# PIC_CONTROLLER.net
KiCad netlist of a schematic drawn in Altium Designer
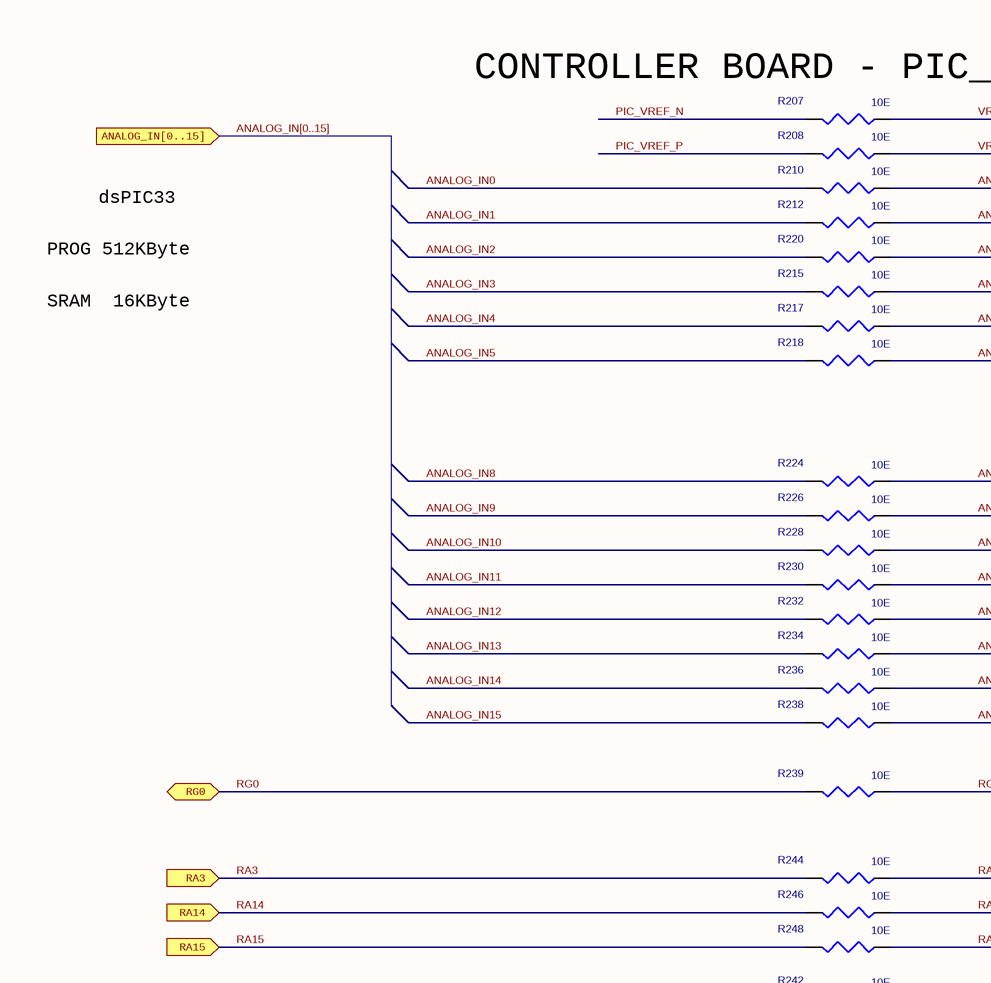
[diagram p0: PIC_CONTROLLER.SchDoc, top left]
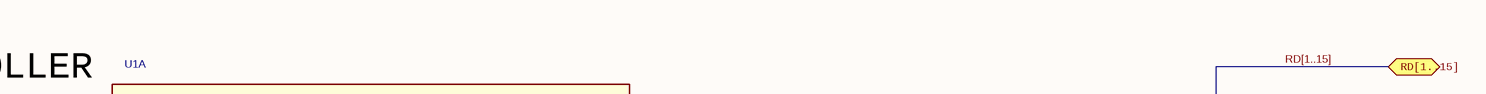
[diagram p1: PIC_CONTROLLER.SchDoc, top right]
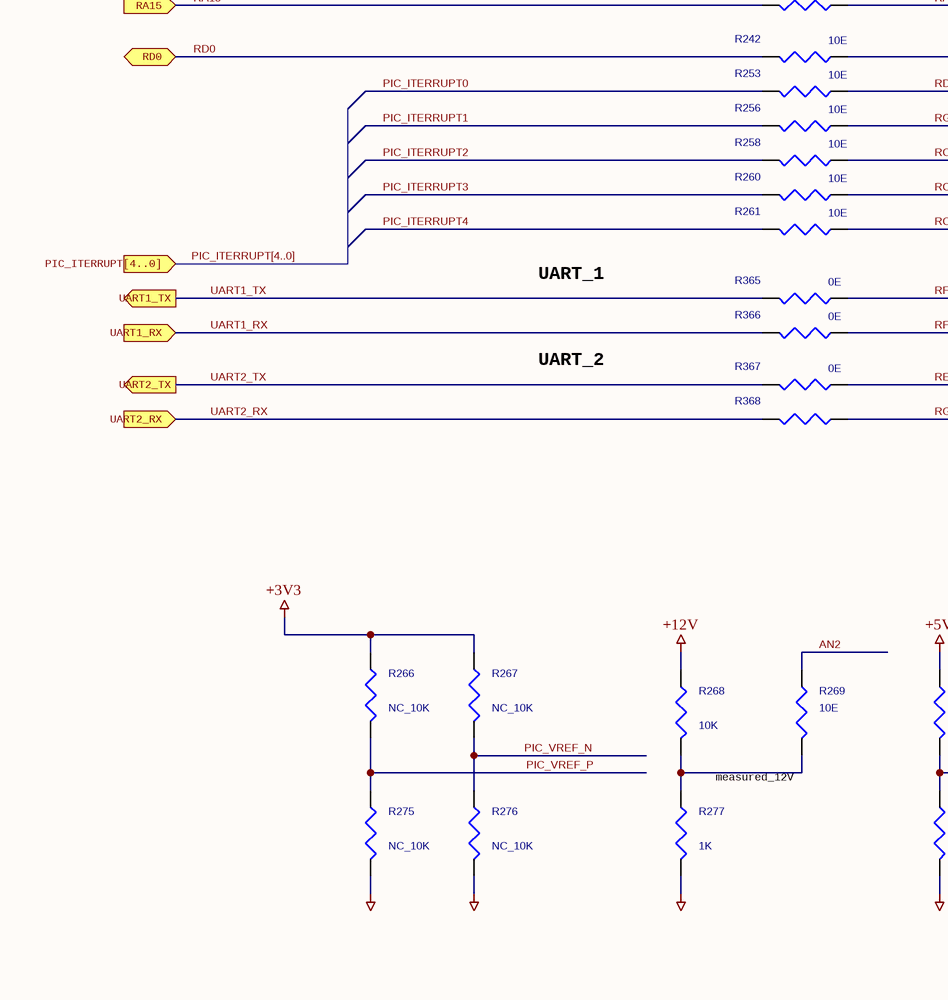
[diagram p2: PIC_CONTROLLER.SchDoc, bottom left]
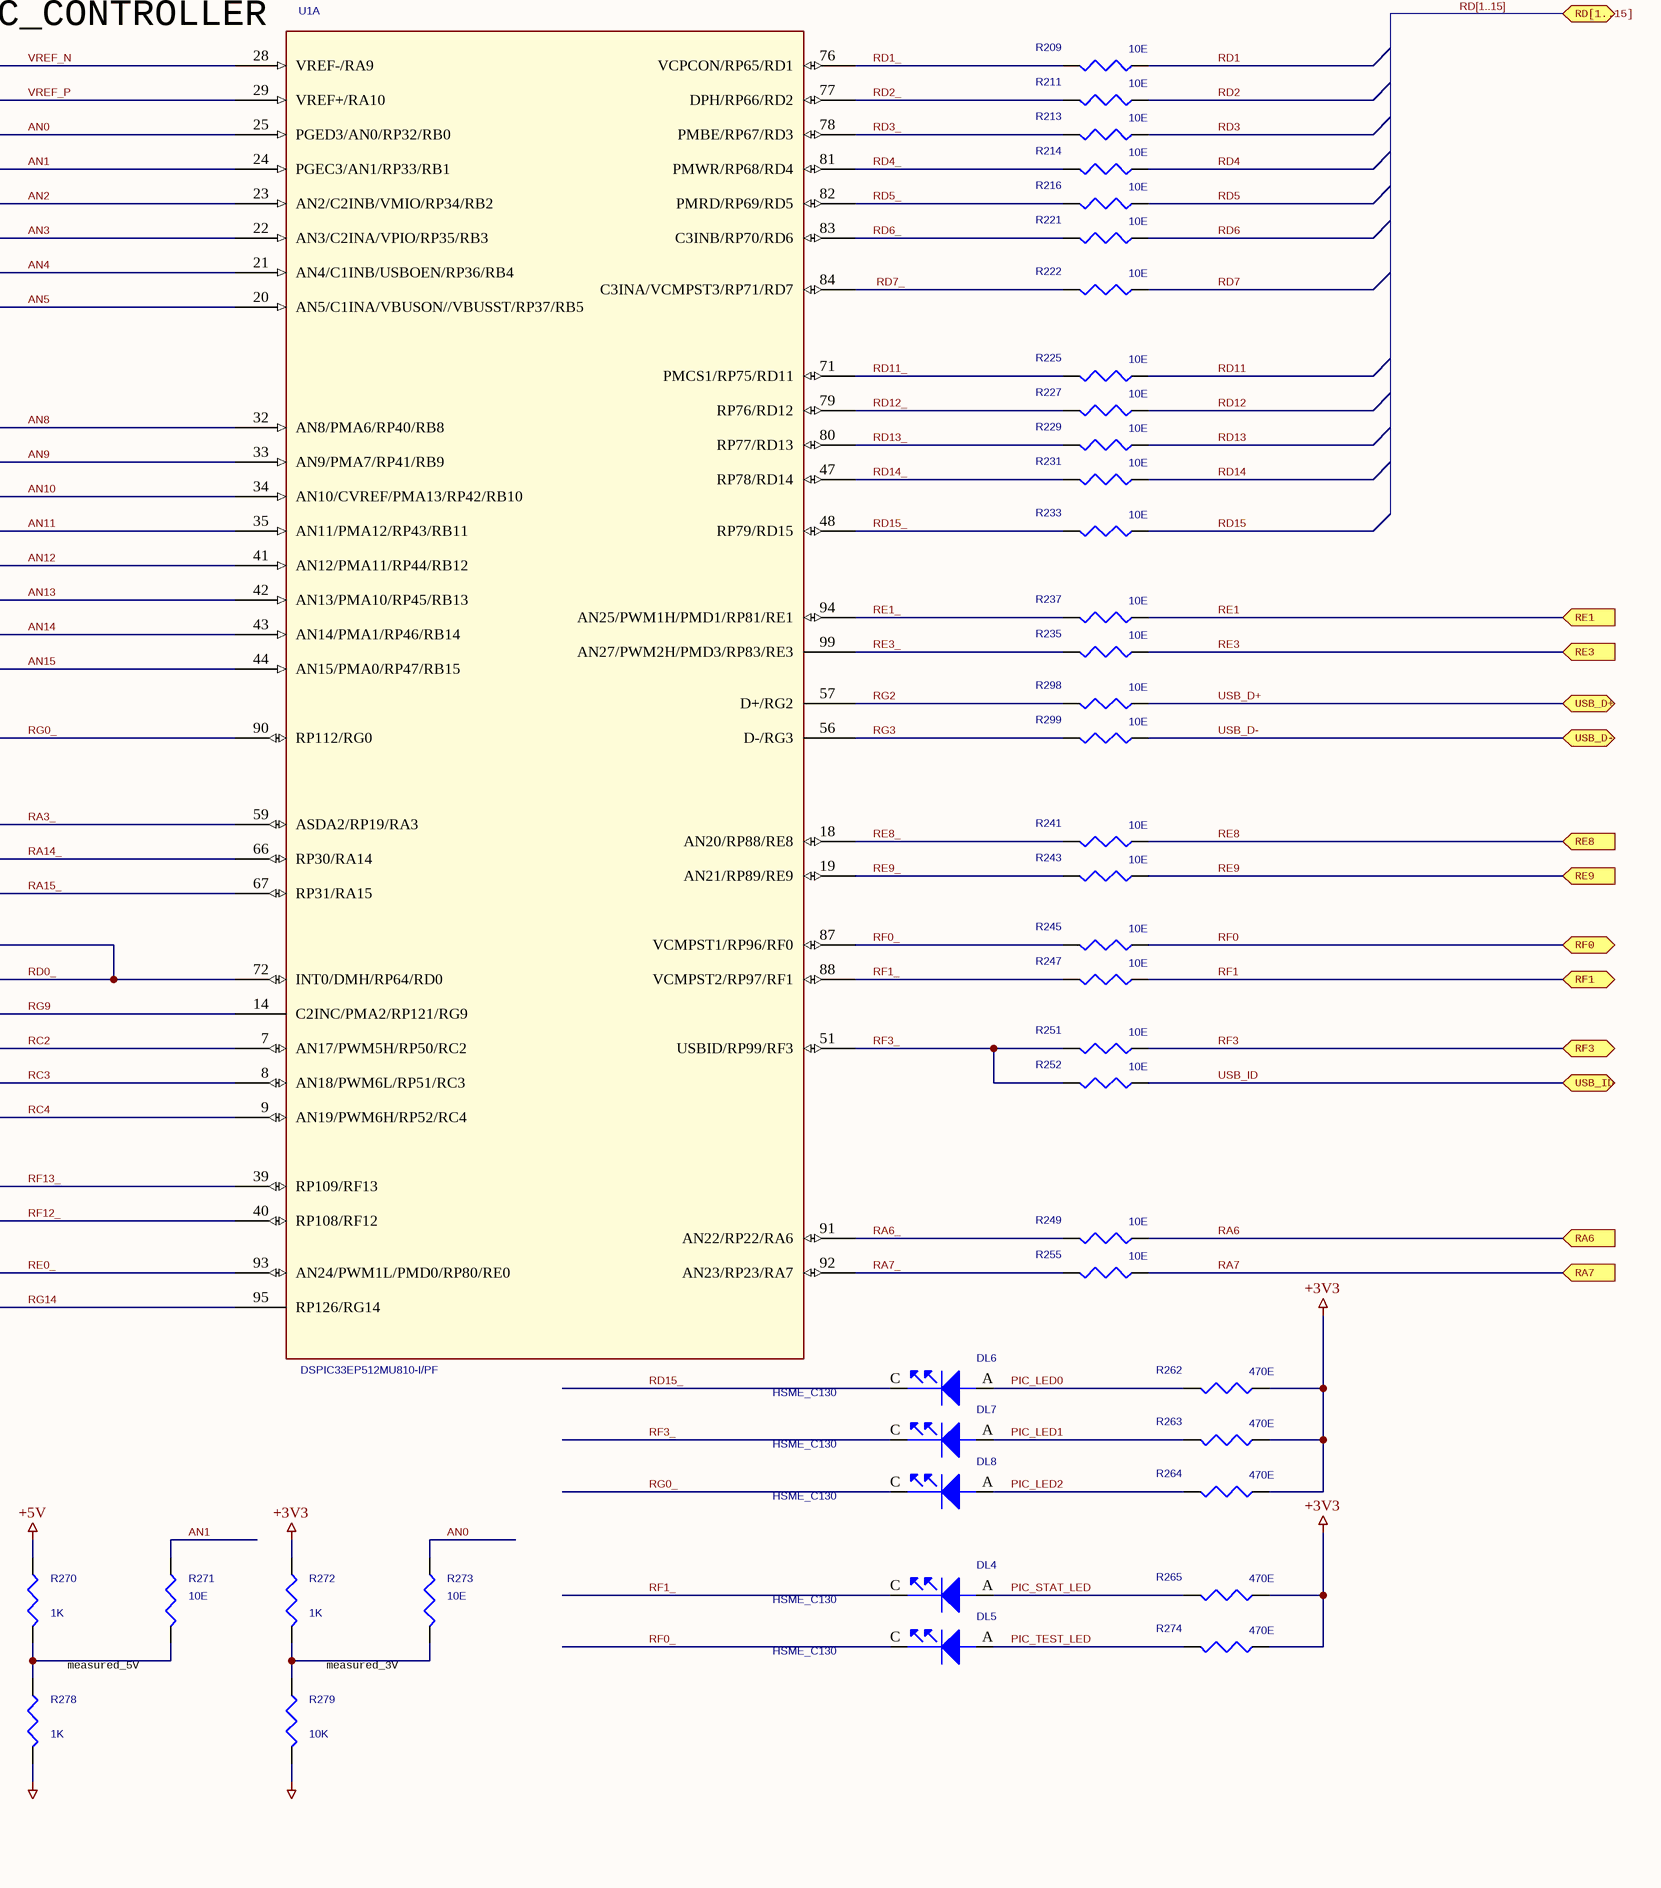
[diagram p3: PIC_CONTROLLER.SchDoc, bottom right]

(export (version "E")
  (design (tool "Eeschema 10.0.6"))
  (components
    (comp (ref "DL4")
      (value "HSME_C130")
      (footprint "LED_0603")
      (fields (field (name "MFG") "AVAGO"))
      (libsource (lib "*") (part "LED"))
    )
    (comp (ref "DL5")
      (value "HSME_C130")
      (footprint "LED_0603")
      (fields (field (name "MFG") "AVAGO"))
      (libsource (lib "*") (part "LED"))
    )
    (comp (ref "DL6")
      (value "HSME_C130")
      (footprint "LED_0603")
      (fields (field (name "MFG") "AVAGO"))
      (libsource (lib "*") (part "LED"))
    )
    (comp (ref "DL7")
      (value "HSME_C130")
      (footprint "LED_0603")
      (fields (field (name "MFG") "AVAGO"))
      (libsource (lib "*") (part "LED"))
    )
    (comp (ref "DL8")
      (value "HSME_C130")
      (footprint "LED_0603")
      (fields (field (name "MFG") "AVAGO"))
      (libsource (lib "*") (part "LED"))
    )
    (comp (ref "R207")
      (value "10E")
      (footprint "0603")
      (fields (field (name "MFG") "YAGEO"))
      (libsource (lib "*") (part "R_Dup1"))
    )
    (comp (ref "R208")
      (value "10E")
      (footprint "0603")
      (fields (field (name "MFG") "YAGEO"))
      (libsource (lib "*") (part "R_Dup1"))
    )
    (comp (ref "R209")
      (value "10E")
      (footprint "0603")
      (fields (field (name "MFG") "YAGEO"))
      (libsource (lib "*") (part "R_Dup1"))
    )
    (comp (ref "R210")
      (value "10E")
      (footprint "0603")
      (fields (field (name "MFG") "YAGEO"))
      (libsource (lib "*") (part "R_Dup1"))
    )
    (comp (ref "R211")
      (value "10E")
      (footprint "0603")
      (fields (field (name "MFG") "YAGEO"))
      (libsource (lib "*") (part "R_Dup1"))
    )
    (comp (ref "R212")
      (value "10E")
      (footprint "0603")
      (fields (field (name "MFG") "YAGEO"))
      (libsource (lib "*") (part "R_Dup1"))
    )
    (comp (ref "R213")
      (value "10E")
      (footprint "0603")
      (fields (field (name "MFG") "YAGEO"))
      (libsource (lib "*") (part "R_Dup1"))
    )
    (comp (ref "R214")
      (value "10E")
      (footprint "0603")
      (fields (field (name "MFG") "YAGEO"))
      (libsource (lib "*") (part "R_Dup1"))
    )
    (comp (ref "R215")
      (value "10E")
      (footprint "0603")
      (fields (field (name "MFG") "YAGEO"))
      (libsource (lib "*") (part "R_Dup1"))
    )
    (comp (ref "R216")
      (value "10E")
      (footprint "0603")
      (fields (field (name "MFG") "YAGEO"))
      (libsource (lib "*") (part "R_Dup1"))
    )
    (comp (ref "R217")
      (value "10E")
      (footprint "0603")
      (fields (field (name "MFG") "YAGEO"))
      (libsource (lib "*") (part "R_Dup1"))
    )
    (comp (ref "R218")
      (value "10E")
      (footprint "0603")
      (fields (field (name "MFG") "YAGEO"))
      (libsource (lib "*") (part "R_Dup1"))
    )
    (comp (ref "R220")
      (value "10E")
      (footprint "0603")
      (fields (field (name "MFG") "YAGEO"))
      (libsource (lib "*") (part "R_Dup1"))
    )
    (comp (ref "R221")
      (value "10E")
      (footprint "0603")
      (fields (field (name "MFG") "YAGEO"))
      (libsource (lib "*") (part "R_Dup1"))
    )
    (comp (ref "R222")
      (value "10E")
      (footprint "0603")
      (fields (field (name "MFG") "YAGEO"))
      (libsource (lib "*") (part "R_Dup1"))
    )
    (comp (ref "R224")
      (value "10E")
      (footprint "0603")
      (fields (field (name "MFG") "YAGEO"))
      (libsource (lib "*") (part "R_Dup1"))
    )
    (comp (ref "R225")
      (value "10E")
      (footprint "0603")
      (fields (field (name "MFG") "YAGEO"))
      (libsource (lib "*") (part "R_Dup1"))
    )
    (comp (ref "R226")
      (value "10E")
      (footprint "0603")
      (fields (field (name "MFG") "YAGEO"))
      (libsource (lib "*") (part "R_Dup1"))
    )
    (comp (ref "R227")
      (value "10E")
      (footprint "0603")
      (fields (field (name "MFG") "YAGEO"))
      (libsource (lib "*") (part "R_Dup1"))
    )
    (comp (ref "R228")
      (value "10E")
      (footprint "0603")
      (fields (field (name "MFG") "YAGEO"))
      (libsource (lib "*") (part "R_Dup1"))
    )
    (comp (ref "R229")
      (value "10E")
      (footprint "0603")
      (fields (field (name "MFG") "YAGEO"))
      (libsource (lib "*") (part "R_Dup1"))
    )
    (comp (ref "R230")
      (value "10E")
      (footprint "0603")
      (fields (field (name "MFG") "YAGEO"))
      (libsource (lib "*") (part "R_Dup1"))
    )
    (comp (ref "R231")
      (value "10E")
      (footprint "0603")
      (fields (field (name "MFG") "YAGEO"))
      (libsource (lib "*") (part "R_Dup1"))
    )
    (comp (ref "R232")
      (value "10E")
      (footprint "0603")
      (fields (field (name "MFG") "YAGEO"))
      (libsource (lib "*") (part "R_Dup1"))
    )
    (comp (ref "R233")
      (value "10E")
      (footprint "0603")
      (fields (field (name "MFG") "YAGEO"))
      (libsource (lib "*") (part "R_Dup1"))
    )
    (comp (ref "R234")
      (value "10E")
      (footprint "0603")
      (fields (field (name "MFG") "YAGEO"))
      (libsource (lib "*") (part "R_Dup1"))
    )
    (comp (ref "R235")
      (value "10E")
      (footprint "0603")
      (fields (field (name "MFG") "YAGEO"))
      (libsource (lib "*") (part "R_Dup1"))
    )
    (comp (ref "R236")
      (value "10E")
      (footprint "0603")
      (fields (field (name "MFG") "YAGEO"))
      (libsource (lib "*") (part "R_Dup1"))
    )
    (comp (ref "R237")
      (value "10E")
      (footprint "0603")
      (fields (field (name "MFG") "YAGEO"))
      (libsource (lib "*") (part "R_Dup1"))
    )
    (comp (ref "R238")
      (value "10E")
      (footprint "0603")
      (fields (field (name "MFG") "YAGEO"))
      (libsource (lib "*") (part "R_Dup1"))
    )
    (comp (ref "R239")
      (value "10E")
      (footprint "0603")
      (fields (field (name "MFG") "YAGEO"))
      (libsource (lib "*") (part "R_Dup1"))
    )
    (comp (ref "R241")
      (value "10E")
      (footprint "0603")
      (fields (field (name "MFG") "YAGEO"))
      (libsource (lib "*") (part "R_Dup1"))
    )
    (comp (ref "R242")
      (value "10E")
      (footprint "0603")
      (fields (field (name "MFG") "YAGEO"))
      (libsource (lib "*") (part "R_Dup1"))
    )
    (comp (ref "R243")
      (value "10E")
      (footprint "0603")
      (fields (field (name "MFG") "YAGEO"))
      (libsource (lib "*") (part "R_Dup1"))
    )
    (comp (ref "R244")
      (value "10E")
      (footprint "0603")
      (fields (field (name "MFG") "YAGEO"))
      (libsource (lib "*") (part "R_Dup1"))
    )
    (comp (ref "R245")
      (value "10E")
      (footprint "0603")
      (fields (field (name "MFG") "YAGEO"))
      (libsource (lib "*") (part "R_Dup1"))
    )
    (comp (ref "R246")
      (value "10E")
      (footprint "0603")
      (fields (field (name "MFG") "YAGEO"))
      (libsource (lib "*") (part "R_Dup1"))
    )
    (comp (ref "R247")
      (value "10E")
      (footprint "0603")
      (fields (field (name "MFG") "YAGEO"))
      (libsource (lib "*") (part "R_Dup1"))
    )
    (comp (ref "R248")
      (value "10E")
      (footprint "0603")
      (fields (field (name "MFG") "YAGEO"))
      (libsource (lib "*") (part "R_Dup1"))
    )
    (comp (ref "R249")
      (value "10E")
      (footprint "0603")
      (fields (field (name "MFG") "YAGEO"))
      (libsource (lib "*") (part "R_Dup1"))
    )
    (comp (ref "R251")
      (value "10E")
      (footprint "0603")
      (fields (field (name "MFG") "YAGEO"))
      (libsource (lib "*") (part "R_Dup1"))
    )
    (comp (ref "R252")
      (value "10E")
      (footprint "0603")
      (fields (field (name "MFG") "YAGEO"))
      (libsource (lib "*") (part "R_Dup1"))
    )
    (comp (ref "R253")
      (value "10E")
      (footprint "0603")
      (fields (field (name "MFG") "YAGEO"))
      (libsource (lib "*") (part "R_Dup1"))
    )
    (comp (ref "R255")
      (value "10E")
      (footprint "0603")
      (fields (field (name "MFG") "YAGEO"))
      (libsource (lib "*") (part "R_Dup1"))
    )
    (comp (ref "R256")
      (value "10E")
      (footprint "0603")
      (fields (field (name "MFG") "YAGEO"))
      (libsource (lib "*") (part "R_Dup1"))
    )
    (comp (ref "R258")
      (value "10E")
      (footprint "0603")
      (fields (field (name "MFG") "YAGEO"))
      (libsource (lib "*") (part "R_Dup1"))
    )
    (comp (ref "R260")
      (value "10E")
      (footprint "0603")
      (fields (field (name "MFG") "YAGEO"))
      (libsource (lib "*") (part "R_Dup1"))
    )
    (comp (ref "R261")
      (value "10E")
      (footprint "0603")
      (fields (field (name "MFG") "YAGEO"))
      (libsource (lib "*") (part "R_Dup1"))
    )
    (comp (ref "R262")
      (value "470E")
      (footprint "0603")
      (fields (field (name "MFG") "YAGEO"))
      (libsource (lib "*") (part "R_Dup1"))
    )
    (comp (ref "R263")
      (value "470E")
      (footprint "0603")
      (fields (field (name "MFG") "YAGEO"))
      (libsource (lib "*") (part "R_Dup1"))
    )
    (comp (ref "R264")
      (value "470E")
      (footprint "0603")
      (fields (field (name "MFG") "YAGEO"))
      (libsource (lib "*") (part "R_Dup1"))
    )
    (comp (ref "R265")
      (value "470E")
      (footprint "0603")
      (fields (field (name "MFG") "YAGEO"))
      (libsource (lib "*") (part "R_Dup1"))
    )
    (comp (ref "R266")
      (value "NC_10K")
      (footprint "0603")
      (fields (field (name "MFG") "YAGEO"))
      (libsource (lib "*") (part "R_Dup1"))
    )
    (comp (ref "R267")
      (value "NC_10K")
      (footprint "0603")
      (fields (field (name "MFG") "YAGEO"))
      (libsource (lib "*") (part "R_Dup1"))
    )
    (comp (ref "R268")
      (value "10K")
      (footprint "0603")
      (fields (field (name "MFG") "YAGEO"))
      (libsource (lib "*") (part "R_Dup1"))
    )
    (comp (ref "R269")
      (value "10E")
      (footprint "0603")
      (fields (field (name "MFG") "YAGEO"))
      (libsource (lib "*") (part "R_Dup1"))
    )
    (comp (ref "R270")
      (value "1K")
      (footprint "0603")
      (fields (field (name "MFG") "YAGEO"))
      (libsource (lib "*") (part "R_Dup1"))
    )
    (comp (ref "R271")
      (value "10E")
      (footprint "0603")
      (fields (field (name "MFG") "YAGEO"))
      (libsource (lib "*") (part "R_Dup1"))
    )
    (comp (ref "R272")
      (value "1K")
      (footprint "0603")
      (fields (field (name "MFG") "YAGEO"))
      (libsource (lib "*") (part "R_Dup1"))
    )
    (comp (ref "R273")
      (value "10E")
      (footprint "0603")
      (fields (field (name "MFG") "YAGEO"))
      (libsource (lib "*") (part "R_Dup1"))
    )
    (comp (ref "R274")
      (value "470E")
      (footprint "0603")
      (fields (field (name "MFG") "YAGEO"))
      (libsource (lib "*") (part "R_Dup1"))
    )
    (comp (ref "R275")
      (value "NC_10K")
      (footprint "0603")
      (fields (field (name "MFG") "YAGEO"))
      (libsource (lib "*") (part "R_Dup1"))
    )
    (comp (ref "R276")
      (value "NC_10K")
      (footprint "0603")
      (fields (field (name "MFG") "YAGEO"))
      (libsource (lib "*") (part "R_Dup1"))
    )
    (comp (ref "R277")
      (value "1K")
      (footprint "0603")
      (fields (field (name "MFG") "YAGEO"))
      (libsource (lib "*") (part "R_Dup1"))
    )
    (comp (ref "R278")
      (value "1K")
      (footprint "0603")
      (fields (field (name "MFG") "YAGEO"))
      (libsource (lib "*") (part "R_Dup1"))
    )
    (comp (ref "R279")
      (value "10K")
      (footprint "0603")
      (fields (field (name "MFG") "YAGEO"))
      (libsource (lib "*") (part "R_Dup1"))
    )
    (comp (ref "R298")
      (value "10E")
      (footprint "0603")
      (fields (field (name "MFG") "YAGEO"))
      (libsource (lib "*") (part "R_Dup1"))
    )
    (comp (ref "R299")
      (value "10E")
      (footprint "0603")
      (fields (field (name "MFG") "YAGEO"))
      (libsource (lib "*") (part "R_Dup1"))
    )
    (comp (ref "R365")
      (value "0E")
      (footprint "0603")
      (fields (field (name "MFG") "YAGEO"))
      (libsource (lib "*") (part "R_Dup1"))
    )
    (comp (ref "R366")
      (value "0E")
      (footprint "0603")
      (fields (field (name "MFG") "YAGEO"))
      (libsource (lib "*") (part "R_Dup1"))
    )
    (comp (ref "R367")
      (value "0E")
      (footprint "0603")
      (fields (field (name "MFG") "YAGEO"))
      (libsource (lib "*") (part "R_Dup1"))
    )
    (comp (ref "R368")
      (value "0E")
      (footprint "0603")
      (fields (field (name "MFG") "YAGEO"))
      (libsource (lib "*") (part "R_Dup1"))
    )
    (comp (ref "U1")
      (value "DSPIC33EP512MU810-I/PF")
      (footprint "TQFP_100")
      (fields (field (name "MFG") "MICROCHIP"))
      (libsource (lib "*") (part "DSPIC33EP512MU810-I/PF_0"))
    )
  )
  (nets
    (net (code "6") (name "+3V3") (class "Default")
      (node (ref "R262") (pin "1") (pinfunction "1_1") (pintype "passive"))
      (node (ref "R263") (pin "1") (pinfunction "1_1") (pintype "passive"))
      (node (ref "R264") (pin "1") (pinfunction "1_1") (pintype "passive"))
      (node (ref "R265") (pin "1") (pinfunction "1_1") (pintype "passive"))
      (node (ref "R266") (pin "1") (pinfunction "1_1") (pintype "passive"))
      (node (ref "R267") (pin "1") (pinfunction "1_1") (pintype "passive"))
      (node (ref "R272") (pin "1") (pinfunction "1_1") (pintype "passive"))
      (node (ref "R274") (pin "1") (pinfunction "1_1") (pintype "passive"))
    )
    (net (code "7") (name "+5V") (class "Default")
      (node (ref "R270") (pin "1") (pinfunction "1_1") (pintype "passive"))
    )
    (net (code "8") (name "+12V") (class "Default")
      (node (ref "R268") (pin "1") (pinfunction "1_1") (pintype "passive"))
    )
    (net (code "9") (name "/AN0") (class "Default")
      (node (ref "R210") (pin "1") (pinfunction "1_1") (pintype "passive"))
      (node (ref "R273") (pin "1") (pinfunction "1_1") (pintype "passive"))
      (node (ref "U1") (pin "25") (pinfunction "PGED3/AN0/RP32/RB0_25") (pintype "input"))
    )
    (net (code "10") (name "/AN1") (class "Default")
      (node (ref "R212") (pin "1") (pinfunction "1_1") (pintype "passive"))
      (node (ref "R271") (pin "1") (pinfunction "1_1") (pintype "passive"))
      (node (ref "U1") (pin "24") (pinfunction "PGEC3/AN1/RP33/RB1_24") (pintype "input"))
    )
    (net (code "11") (name "/AN2") (class "Default")
      (node (ref "R220") (pin "1") (pinfunction "1_1") (pintype "passive"))
      (node (ref "R269") (pin "1") (pinfunction "1_1") (pintype "passive"))
      (node (ref "U1") (pin "23") (pinfunction "AN2/C2INB/VMIO/RP34/RB2_23") (pintype "input"))
    )
    (net (code "12") (name "/AN3") (class "Default")
      (node (ref "R215") (pin "1") (pinfunction "1_1") (pintype "passive"))
      (node (ref "U1") (pin "22") (pinfunction "AN3/C2INA/VPIO/RP35/RB3_22") (pintype "input"))
    )
    (net (code "13") (name "/AN4") (class "Default")
      (node (ref "R217") (pin "1") (pinfunction "1_1") (pintype "passive"))
      (node (ref "U1") (pin "21") (pinfunction "AN4/C1INB/USBOEN/RP36/RB4_21") (pintype "input"))
    )
    (net (code "14") (name "/AN5") (class "Default")
      (node (ref "R218") (pin "1") (pinfunction "1_1") (pintype "passive"))
      (node (ref "U1") (pin "20") (pinfunction "AN5/C1INA/VBUSON//VBUSST/RP37/RB5_20") (pintype "input"))
    )
    (net (code "15") (name "/AN8") (class "Default")
      (node (ref "R224") (pin "1") (pinfunction "1_1") (pintype "passive"))
      (node (ref "U1") (pin "32") (pinfunction "AN8/PMA6/RP40/RB8_32") (pintype "input"))
    )
    (net (code "16") (name "/AN9") (class "Default")
      (node (ref "R226") (pin "1") (pinfunction "1_1") (pintype "passive"))
      (node (ref "U1") (pin "33") (pinfunction "AN9/PMA7/RP41/RB9_33") (pintype "input"))
    )
    (net (code "17") (name "/AN10") (class "Default")
      (node (ref "R228") (pin "1") (pinfunction "1_1") (pintype "passive"))
      (node (ref "U1") (pin "34") (pinfunction "AN10/CVREF/PMA13/RP42/RB10_34") (pintype "input"))
    )
    (net (code "18") (name "/AN11") (class "Default")
      (node (ref "R230") (pin "1") (pinfunction "1_1") (pintype "passive"))
      (node (ref "U1") (pin "35") (pinfunction "AN11/PMA12/RP43/RB11_35") (pintype "input"))
    )
    (net (code "19") (name "/AN12") (class "Default")
      (node (ref "R232") (pin "1") (pinfunction "1_1") (pintype "passive"))
      (node (ref "U1") (pin "41") (pinfunction "AN12/PMA11/RP44/RB12_41") (pintype "input"))
    )
    (net (code "20") (name "/AN13") (class "Default")
      (node (ref "R234") (pin "1") (pinfunction "1_1") (pintype "passive"))
      (node (ref "U1") (pin "42") (pinfunction "AN13/PMA10/RP45/RB13_42") (pintype "input"))
    )
    (net (code "21") (name "/AN14") (class "Default")
      (node (ref "R236") (pin "1") (pinfunction "1_1") (pintype "passive"))
      (node (ref "U1") (pin "43") (pinfunction "AN14/PMA1/RP46/RB14_43") (pintype "input"))
    )
    (net (code "22") (name "/AN15") (class "Default")
      (node (ref "R238") (pin "1") (pinfunction "1_1") (pintype "passive"))
      (node (ref "U1") (pin "44") (pinfunction "AN15/PMA0/RP47/RB15_44") (pintype "input"))
    )
    (net (code "23") (name "/ANALOG_IN0") (class "Default")
      (node (ref "R210") (pin "2") (pinfunction "2_2") (pintype "passive"))
    )
    (net (code "24") (name "/ANALOG_IN1") (class "Default")
      (node (ref "R212") (pin "2") (pinfunction "2_2") (pintype "passive"))
    )
    (net (code "25") (name "/ANALOG_IN2") (class "Default")
      (node (ref "R220") (pin "2") (pinfunction "2_2") (pintype "passive"))
    )
    (net (code "26") (name "/ANALOG_IN3") (class "Default")
      (node (ref "R215") (pin "2") (pinfunction "2_2") (pintype "passive"))
    )
    (net (code "27") (name "/ANALOG_IN4") (class "Default")
      (node (ref "R217") (pin "2") (pinfunction "2_2") (pintype "passive"))
    )
    (net (code "28") (name "/ANALOG_IN5") (class "Default")
      (node (ref "R218") (pin "2") (pinfunction "2_2") (pintype "passive"))
    )
    (net (code "29") (name "/ANALOG_IN8") (class "Default")
      (node (ref "R224") (pin "2") (pinfunction "2_2") (pintype "passive"))
    )
    (net (code "30") (name "/ANALOG_IN9") (class "Default")
      (node (ref "R226") (pin "2") (pinfunction "2_2") (pintype "passive"))
    )
    (net (code "31") (name "/ANALOG_IN10") (class "Default")
      (node (ref "R228") (pin "2") (pinfunction "2_2") (pintype "passive"))
    )
    (net (code "32") (name "/ANALOG_IN11") (class "Default")
      (node (ref "R230") (pin "2") (pinfunction "2_2") (pintype "passive"))
    )
    (net (code "33") (name "/ANALOG_IN12") (class "Default")
      (node (ref "R232") (pin "2") (pinfunction "2_2") (pintype "passive"))
    )
    (net (code "34") (name "/ANALOG_IN13") (class "Default")
      (node (ref "R234") (pin "2") (pinfunction "2_2") (pintype "passive"))
    )
    (net (code "35") (name "/ANALOG_IN14") (class "Default")
      (node (ref "R236") (pin "2") (pinfunction "2_2") (pintype "passive"))
    )
    (net (code "36") (name "/ANALOG_IN15") (class "Default")
      (node (ref "R238") (pin "2") (pinfunction "2_2") (pintype "passive"))
    )
    (net (code "38") (name "/PIC_ITERRUPT0") (class "Default")
      (node (ref "R253") (pin "2") (pinfunction "2_2") (pintype "passive"))
    )
    (net (code "39") (name "/PIC_ITERRUPT1") (class "Default")
      (node (ref "R256") (pin "2") (pinfunction "2_2") (pintype "passive"))
    )
    (net (code "40") (name "/PIC_ITERRUPT2") (class "Default")
      (node (ref "R258") (pin "2") (pinfunction "2_2") (pintype "passive"))
    )
    (net (code "41") (name "/PIC_ITERRUPT3") (class "Default")
      (node (ref "R260") (pin "2") (pinfunction "2_2") (pintype "passive"))
    )
    (net (code "42") (name "/PIC_ITERRUPT4") (class "Default")
      (node (ref "R261") (pin "2") (pinfunction "2_2") (pintype "passive"))
    )
    (net (code "44") (name "/PIC_LED0") (class "Default")
      (node (ref "DL6") (pin "A") (pinfunction "ANODE_A") (pintype "passive"))
      (node (ref "R262") (pin "2") (pinfunction "2_2") (pintype "passive"))
    )
    (net (code "45") (name "/PIC_LED1") (class "Default")
      (node (ref "DL7") (pin "A") (pinfunction "ANODE_A") (pintype "passive"))
      (node (ref "R263") (pin "2") (pinfunction "2_2") (pintype "passive"))
    )
    (net (code "46") (name "/PIC_LED2") (class "Default")
      (node (ref "DL8") (pin "A") (pinfunction "ANODE_A") (pintype "passive"))
      (node (ref "R264") (pin "2") (pinfunction "2_2") (pintype "passive"))
    )
    (net (code "47") (name "/PIC_STAT_LED") (class "Default")
      (node (ref "DL4") (pin "A") (pinfunction "ANODE_A") (pintype "passive"))
      (node (ref "R265") (pin "2") (pinfunction "2_2") (pintype "passive"))
    )
    (net (code "48") (name "/PIC_TEST_LED") (class "Default")
      (node (ref "DL5") (pin "A") (pinfunction "ANODE_A") (pintype "passive"))
      (node (ref "R274") (pin "2") (pinfunction "2_2") (pintype "passive"))
    )
    (net (code "49") (name "/PIC_VREF_N") (class "Default")
      (node (ref "R207") (pin "2") (pinfunction "2_2") (pintype "passive"))
      (node (ref "R267") (pin "2") (pinfunction "2_2") (pintype "passive"))
      (node (ref "R276") (pin "1") (pinfunction "1_1") (pintype "passive"))
    )
    (net (code "50") (name "/PIC_VREF_P") (class "Default")
      (node (ref "R208") (pin "2") (pinfunction "2_2") (pintype "passive"))
      (node (ref "R266") (pin "2") (pinfunction "2_2") (pintype "passive"))
      (node (ref "R275") (pin "1") (pinfunction "1_1") (pintype "passive"))
    )
    (net (code "51") (name "/RA3") (class "Default")
      (node (ref "R244") (pin "2") (pinfunction "2_2") (pintype "passive"))
    )
    (net (code "52") (name "/RA3_") (class "Default")
      (node (ref "R244") (pin "1") (pinfunction "1_1") (pintype "passive"))
      (node (ref "U1") (pin "59") (pinfunction "ASDA2/RP19/RA3_59") (pintype "bidirectional"))
    )
    (net (code "53") (name "/RA6") (class "Default")
      (node (ref "R249") (pin "1") (pinfunction "1_1") (pintype "passive"))
    )
    (net (code "54") (name "/RA6_") (class "Default")
      (node (ref "R249") (pin "2") (pinfunction "2_2") (pintype "passive"))
      (node (ref "U1") (pin "91") (pinfunction "AN22/RP22/RA6_91") (pintype "bidirectional"))
    )
    (net (code "55") (name "/RA7") (class "Default")
      (node (ref "R255") (pin "1") (pinfunction "1_1") (pintype "passive"))
    )
    (net (code "56") (name "/RA7_") (class "Default")
      (node (ref "R255") (pin "2") (pinfunction "2_2") (pintype "passive"))
      (node (ref "U1") (pin "92") (pinfunction "AN23/RP23/RA7_92") (pintype "bidirectional"))
    )
    (net (code "57") (name "/RA14") (class "Default")
      (node (ref "R246") (pin "2") (pinfunction "2_2") (pintype "passive"))
    )
    (net (code "58") (name "/RA14_") (class "Default")
      (node (ref "R246") (pin "1") (pinfunction "1_1") (pintype "passive"))
      (node (ref "U1") (pin "66") (pinfunction "RP30/RA14_66") (pintype "bidirectional"))
    )
    (net (code "59") (name "/RA15") (class "Default")
      (node (ref "R248") (pin "2") (pinfunction "2_2") (pintype "passive"))
    )
    (net (code "60") (name "/RA15_") (class "Default")
      (node (ref "R248") (pin "1") (pinfunction "1_1") (pintype "passive"))
      (node (ref "U1") (pin "67") (pinfunction "RP31/RA15_67") (pintype "bidirectional"))
    )
    (net (code "61") (name "/RC2") (class "Default")
      (node (ref "R258") (pin "1") (pinfunction "1_1") (pintype "passive"))
      (node (ref "U1") (pin "7") (pinfunction "AN17/PWM5H/RP50/RC2_7") (pintype "bidirectional"))
    )
    (net (code "62") (name "/RC3") (class "Default")
      (node (ref "R260") (pin "1") (pinfunction "1_1") (pintype "passive"))
      (node (ref "U1") (pin "8") (pinfunction "AN18/PWM6L/RP51/RC3_8") (pintype "bidirectional"))
    )
    (net (code "63") (name "/RC4") (class "Default")
      (node (ref "R261") (pin "1") (pinfunction "1_1") (pintype "passive"))
      (node (ref "U1") (pin "9") (pinfunction "AN19/PWM6H/RP52/RC4_9") (pintype "bidirectional"))
    )
    (net (code "64") (name "/RD0") (class "Default")
      (node (ref "R242") (pin "2") (pinfunction "2_2") (pintype "passive"))
    )
    (net (code "65") (name "/RD0_") (class "Default")
      (node (ref "R242") (pin "1") (pinfunction "1_1") (pintype "passive"))
      (node (ref "R253") (pin "1") (pinfunction "1_1") (pintype "passive"))
      (node (ref "U1") (pin "72") (pinfunction "INT0/DMH/RP64/RD0_72") (pintype "bidirectional"))
    )
    (net (code "66") (name "/RD1") (class "Default")
      (node (ref "R209") (pin "1") (pinfunction "1_1") (pintype "passive"))
    )
    (net (code "67") (name "/RD1_") (class "Default")
      (node (ref "R209") (pin "2") (pinfunction "2_2") (pintype "passive"))
      (node (ref "U1") (pin "76") (pinfunction "VCPCON/RP65/RD1_76") (pintype "bidirectional"))
    )
    (net (code "68") (name "/RD2") (class "Default")
      (node (ref "R211") (pin "1") (pinfunction "1_1") (pintype "passive"))
    )
    (net (code "69") (name "/RD2_") (class "Default")
      (node (ref "R211") (pin "2") (pinfunction "2_2") (pintype "passive"))
      (node (ref "U1") (pin "77") (pinfunction "DPH/RP66/RD2_77") (pintype "bidirectional"))
    )
    (net (code "70") (name "/RD3") (class "Default")
      (node (ref "R213") (pin "1") (pinfunction "1_1") (pintype "passive"))
    )
    (net (code "71") (name "/RD3_") (class "Default")
      (node (ref "R213") (pin "2") (pinfunction "2_2") (pintype "passive"))
      (node (ref "U1") (pin "78") (pinfunction "PMBE/RP67/RD3_78") (pintype "bidirectional"))
    )
    (net (code "72") (name "/RD4") (class "Default")
      (node (ref "R214") (pin "1") (pinfunction "1_1") (pintype "passive"))
    )
    (net (code "73") (name "/RD4_") (class "Default")
      (node (ref "R214") (pin "2") (pinfunction "2_2") (pintype "passive"))
      (node (ref "U1") (pin "81") (pinfunction "PMWR/RP68/RD4_81") (pintype "bidirectional"))
    )
    (net (code "74") (name "/RD5") (class "Default")
      (node (ref "R216") (pin "1") (pinfunction "1_1") (pintype "passive"))
    )
    (net (code "75") (name "/RD5_") (class "Default")
      (node (ref "R216") (pin "2") (pinfunction "2_2") (pintype "passive"))
      (node (ref "U1") (pin "82") (pinfunction "PMRD/RP69/RD5_82") (pintype "bidirectional"))
    )
    (net (code "76") (name "/RD6") (class "Default")
      (node (ref "R221") (pin "1") (pinfunction "1_1") (pintype "passive"))
    )
    (net (code "77") (name "/RD6_") (class "Default")
      (node (ref "R221") (pin "2") (pinfunction "2_2") (pintype "passive"))
      (node (ref "U1") (pin "83") (pinfunction "C3INB/RP70/RD6_83") (pintype "bidirectional"))
    )
    (net (code "78") (name "/RD7") (class "Default")
      (node (ref "R222") (pin "1") (pinfunction "1_1") (pintype "passive"))
    )
    (net (code "79") (name "/RD7_") (class "Default")
      (node (ref "R222") (pin "2") (pinfunction "2_2") (pintype "passive"))
      (node (ref "U1") (pin "84") (pinfunction "C3INA/VCMPST3/RP71/RD7_84") (pintype "bidirectional"))
    )
    (net (code "80") (name "/RD11") (class "Default")
      (node (ref "R225") (pin "1") (pinfunction "1_1") (pintype "passive"))
    )
    (net (code "81") (name "/RD11_") (class "Default")
      (node (ref "R225") (pin "2") (pinfunction "2_2") (pintype "passive"))
      (node (ref "U1") (pin "71") (pinfunction "PMCS1/RP75/RD11_71") (pintype "bidirectional"))
    )
    (net (code "82") (name "/RD12") (class "Default")
      (node (ref "R227") (pin "1") (pinfunction "1_1") (pintype "passive"))
    )
    (net (code "83") (name "/RD12_") (class "Default")
      (node (ref "R227") (pin "2") (pinfunction "2_2") (pintype "passive"))
      (node (ref "U1") (pin "79") (pinfunction "RP76/RD12_79") (pintype "bidirectional"))
    )
    (net (code "84") (name "/RD13") (class "Default")
      (node (ref "R229") (pin "1") (pinfunction "1_1") (pintype "passive"))
    )
    (net (code "85") (name "/RD13_") (class "Default")
      (node (ref "R229") (pin "2") (pinfunction "2_2") (pintype "passive"))
      (node (ref "U1") (pin "80") (pinfunction "RP77/RD13_80") (pintype "bidirectional"))
    )
    (net (code "86") (name "/RD14") (class "Default")
      (node (ref "R231") (pin "1") (pinfunction "1_1") (pintype "passive"))
    )
    (net (code "87") (name "/RD14_") (class "Default")
      (node (ref "R231") (pin "2") (pinfunction "2_2") (pintype "passive"))
      (node (ref "U1") (pin "47") (pinfunction "RP78/RD14_47") (pintype "bidirectional"))
    )
    (net (code "88") (name "/RD15") (class "Default")
      (node (ref "R233") (pin "1") (pinfunction "1_1") (pintype "passive"))
    )
    (net (code "89") (name "/RD15_") (class "Default")
      (node (ref "DL6") (pin "C") (pinfunction "CATHODE_C") (pintype "passive"))
      (node (ref "R233") (pin "2") (pinfunction "2_2") (pintype "passive"))
      (node (ref "U1") (pin "48") (pinfunction "RP79/RD15_48") (pintype "bidirectional"))
    )
    (net (code "91") (name "/RE0_") (class "Default")
      (node (ref "R367") (pin "1") (pinfunction "1_1") (pintype "passive"))
      (node (ref "U1") (pin "93") (pinfunction "AN24/PWM1L/PMD0/RP80/RE0_93") (pintype "bidirectional"))
    )
    (net (code "92") (name "/RE1") (class "Default")
      (node (ref "R237") (pin "1") (pinfunction "1_1") (pintype "passive"))
    )
    (net (code "93") (name "/RE1_") (class "Default")
      (node (ref "R237") (pin "2") (pinfunction "2_2") (pintype "passive"))
      (node (ref "U1") (pin "94") (pinfunction "AN25/PWM1H/PMD1/RP81/RE1_94") (pintype "bidirectional"))
    )
    (net (code "94") (name "/RE3") (class "Default")
      (node (ref "R235") (pin "1") (pinfunction "1_1") (pintype "passive"))
    )
    (net (code "95") (name "/RE3_") (class "Default")
      (node (ref "R235") (pin "2") (pinfunction "2_2") (pintype "passive"))
      (node (ref "U1") (pin "99") (pinfunction "AN27/PWM2H/PMD3/RP83/RE3_99") (pintype "passive"))
    )
    (net (code "96") (name "/RE8") (class "Default")
      (node (ref "R241") (pin "1") (pinfunction "1_1") (pintype "passive"))
    )
    (net (code "97") (name "/RE8_") (class "Default")
      (node (ref "R241") (pin "2") (pinfunction "2_2") (pintype "passive"))
      (node (ref "U1") (pin "18") (pinfunction "AN20/RP88/RE8_18") (pintype "bidirectional"))
    )
    (net (code "98") (name "/RE9") (class "Default")
      (node (ref "R243") (pin "1") (pinfunction "1_1") (pintype "passive"))
    )
    (net (code "99") (name "/RE9_") (class "Default")
      (node (ref "R243") (pin "2") (pinfunction "2_2") (pintype "passive"))
      (node (ref "U1") (pin "19") (pinfunction "AN21/RP89/RE9_19") (pintype "bidirectional"))
    )
    (net (code "100") (name "/RF0") (class "Default")
      (node (ref "R245") (pin "1") (pinfunction "1_1") (pintype "passive"))
    )
    (net (code "101") (name "/RF0_") (class "Default")
      (node (ref "DL5") (pin "C") (pinfunction "CATHODE_C") (pintype "passive"))
      (node (ref "R245") (pin "2") (pinfunction "2_2") (pintype "passive"))
      (node (ref "U1") (pin "87") (pinfunction "VCMPST1/RP96/RF0_87") (pintype "bidirectional"))
    )
    (net (code "102") (name "/RF1") (class "Default")
      (node (ref "R247") (pin "1") (pinfunction "1_1") (pintype "passive"))
    )
    (net (code "103") (name "/RF1_") (class "Default")
      (node (ref "DL4") (pin "C") (pinfunction "CATHODE_C") (pintype "passive"))
      (node (ref "R247") (pin "2") (pinfunction "2_2") (pintype "passive"))
      (node (ref "U1") (pin "88") (pinfunction "VCMPST2/RP97/RF1_88") (pintype "bidirectional"))
    )
    (net (code "104") (name "/RF3") (class "Default")
      (node (ref "R251") (pin "1") (pinfunction "1_1") (pintype "passive"))
    )
    (net (code "105") (name "/RF3_") (class "Default")
      (node (ref "DL7") (pin "C") (pinfunction "CATHODE_C") (pintype "passive"))
      (node (ref "R251") (pin "2") (pinfunction "2_2") (pintype "passive"))
      (node (ref "R252") (pin "2") (pinfunction "2_2") (pintype "passive"))
      (node (ref "U1") (pin "51") (pinfunction "USBID/RP99/RF3_51") (pintype "bidirectional"))
    )
    (net (code "106") (name "/RF12_") (class "Default")
      (node (ref "R366") (pin "1") (pinfunction "1_1") (pintype "passive"))
      (node (ref "U1") (pin "40") (pinfunction "RP108/RF12_40") (pintype "bidirectional"))
    )
    (net (code "107") (name "/RF13_") (class "Default")
      (node (ref "R365") (pin "1") (pinfunction "1_1") (pintype "passive"))
      (node (ref "U1") (pin "39") (pinfunction "RP109/RF13_39") (pintype "bidirectional"))
    )
    (net (code "108") (name "/RG0") (class "Default")
      (node (ref "R239") (pin "2") (pinfunction "2_2") (pintype "passive"))
    )
    (net (code "109") (name "/RG0_") (class "Default")
      (node (ref "DL8") (pin "C") (pinfunction "CATHODE_C") (pintype "passive"))
      (node (ref "R239") (pin "1") (pinfunction "1_1") (pintype "passive"))
      (node (ref "U1") (pin "90") (pinfunction "RP112/RG0_90") (pintype "bidirectional"))
    )
    (net (code "110") (name "/RG2") (class "Default")
      (node (ref "R298") (pin "2") (pinfunction "2_2") (pintype "passive"))
      (node (ref "U1") (pin "57") (pinfunction "D+/RG2_57") (pintype "passive"))
    )
    (net (code "111") (name "/RG3") (class "Default")
      (node (ref "R299") (pin "2") (pinfunction "2_2") (pintype "passive"))
      (node (ref "U1") (pin "56") (pinfunction "D-/RG3_56") (pintype "passive"))
    )
    (net (code "112") (name "/RG9") (class "Default")
      (node (ref "R256") (pin "1") (pinfunction "1_1") (pintype "passive"))
      (node (ref "U1") (pin "14") (pinfunction "C2INC/PMA2/RP121/RG9_14") (pintype "passive"))
    )
    (net (code "113") (name "/RG14") (class "Default")
      (node (ref "R368") (pin "1") (pinfunction "1_1") (pintype "passive"))
      (node (ref "U1") (pin "95") (pinfunction "RP126/RG14_95") (pintype "passive"))
    )
    (net (code "114") (name "/UART1_RX") (class "Default")
      (node (ref "R366") (pin "2") (pinfunction "2_2") (pintype "passive"))
    )
    (net (code "115") (name "/UART1_TX") (class "Default")
      (node (ref "R365") (pin "2") (pinfunction "2_2") (pintype "passive"))
    )
    (net (code "116") (name "/UART2_RX") (class "Default")
      (node (ref "R368") (pin "2") (pinfunction "2_2") (pintype "passive"))
    )
    (net (code "117") (name "/UART2_TX") (class "Default")
      (node (ref "R367") (pin "2") (pinfunction "2_2") (pintype "passive"))
    )
    (net (code "118") (name "/USB_D+") (class "Default")
      (node (ref "R298") (pin "1") (pinfunction "1_1") (pintype "passive"))
    )
    (net (code "119") (name "/USB_D-") (class "Default")
      (node (ref "R299") (pin "1") (pinfunction "1_1") (pintype "passive"))
    )
    (net (code "120") (name "/USB_ID") (class "Default")
      (node (ref "R252") (pin "1") (pinfunction "1_1") (pintype "passive"))
    )
    (net (code "121") (name "/VREF_N") (class "Default")
      (node (ref "R207") (pin "1") (pinfunction "1_1") (pintype "passive"))
      (node (ref "U1") (pin "28") (pinfunction "VREF-/RA9_28") (pintype "input"))
    )
    (net (code "122") (name "/VREF_P") (class "Default")
      (node (ref "R208") (pin "1") (pinfunction "1_1") (pintype "passive"))
      (node (ref "U1") (pin "29") (pinfunction "VREF+/RA10_29") (pintype "input"))
    )
    (net (code "123") (name "GND_CPU") (class "Default")
      (node (ref "R275") (pin "2") (pinfunction "2_2") (pintype "passive"))
      (node (ref "R276") (pin "2") (pinfunction "2_2") (pintype "passive"))
      (node (ref "R277") (pin "2") (pinfunction "2_2") (pintype "passive"))
      (node (ref "R278") (pin "2") (pinfunction "2_2") (pintype "passive"))
      (node (ref "R279") (pin "2") (pinfunction "2_2") (pintype "passive"))
    )
    (net (code "124") (name "Net-(R268-Pad2)") (class "Default")
      (node (ref "R268") (pin "2") (pinfunction "2_2") (pintype "passive"))
      (node (ref "R269") (pin "2") (pinfunction "2_2") (pintype "passive"))
      (node (ref "R277") (pin "1") (pinfunction "1_1") (pintype "passive"))
    )
    (net (code "125") (name "Net-(R270-Pad2)") (class "Default")
      (node (ref "R270") (pin "2") (pinfunction "2_2") (pintype "passive"))
      (node (ref "R271") (pin "2") (pinfunction "2_2") (pintype "passive"))
      (node (ref "R278") (pin "1") (pinfunction "1_1") (pintype "passive"))
    )
    (net (code "126") (name "Net-(R272-Pad2)") (class "Default")
      (node (ref "R272") (pin "2") (pinfunction "2_2") (pintype "passive"))
      (node (ref "R273") (pin "2") (pinfunction "2_2") (pintype "passive"))
      (node (ref "R279") (pin "1") (pinfunction "1_1") (pintype "passive"))
    )
  )
)
